# TQFP-100_to_breadboard-100.net
KiCad netlist of a schematic drawn in EAGLE
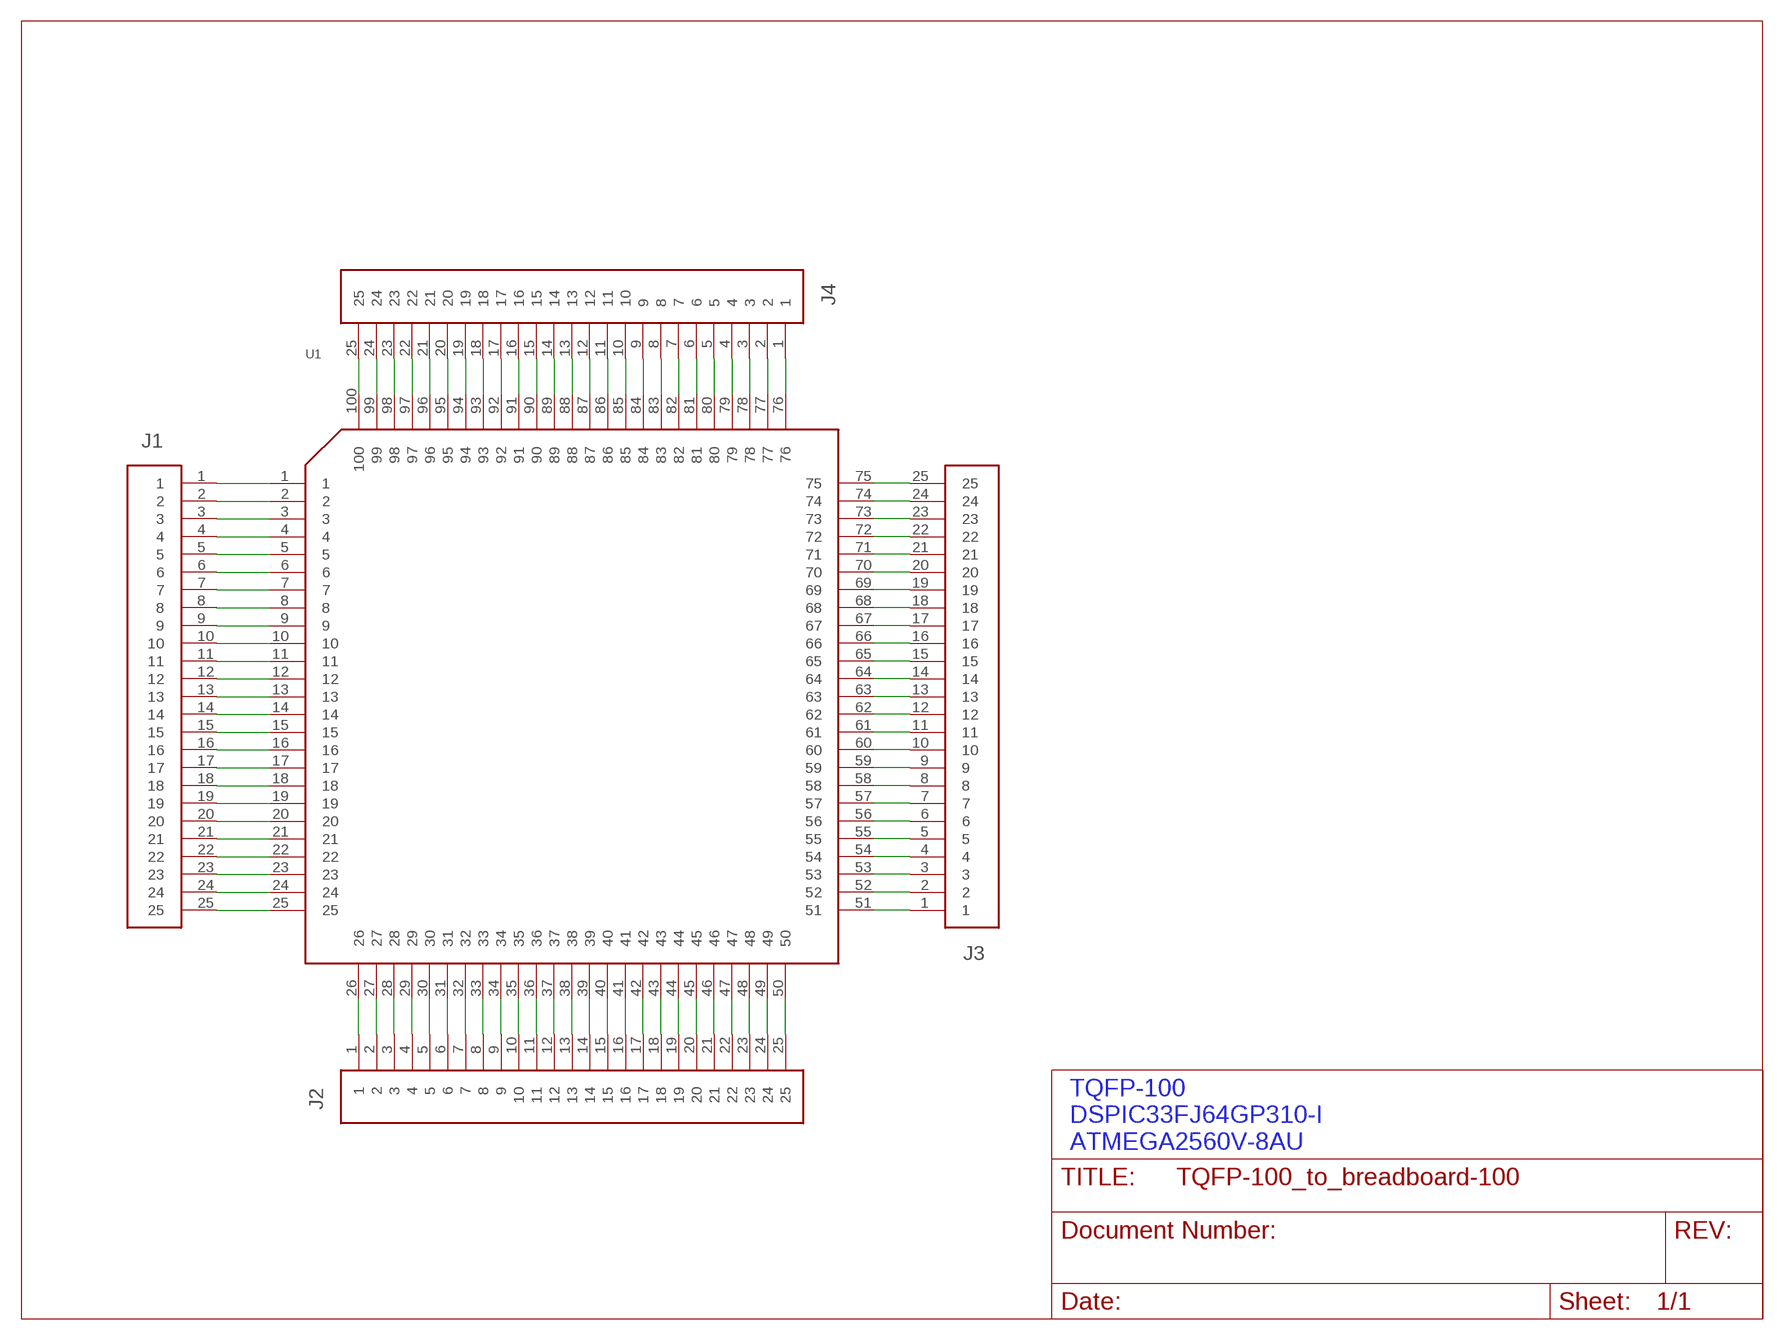
[diagram p0: schematic, sheet 1]

(export (version "E")
  (design (tool "Eeschema 10.0.6"))
  (components
    (comp (ref "J1")
      (value "CONNECTOR_25")
      (footprint "eagle-import:68000-125HLF")
      (libsource (lib "eagle-import") (part "CONNECTOR_25"))
    )
    (comp (ref "J2")
      (value "CONNECTOR_25_NO_SQUARE")
      (footprint "eagle-import:68000-125HLF_NO_SQUARE")
      (libsource (lib "eagle-import") (part "CONNECTOR_25_NO_SQUARE"))
    )
    (comp (ref "J3")
      (value "CONNECTOR_25_NO_SQUARE")
      (footprint "eagle-import:68000-125HLF_NO_SQUARE")
      (libsource (lib "eagle-import") (part "CONNECTOR_25_NO_SQUARE"))
    )
    (comp (ref "J4")
      (value "CONNECTOR_25_NO_SQUARE")
      (footprint "eagle-import:68000-125HLF_NO_SQUARE")
      (libsource (lib "eagle-import") (part "CONNECTOR_25_NO_SQUARE"))
    )
    (comp (ref "U1")
      (value "IC-GENERIC-100-TQFP")
      (footprint "eagle-import:QFP40P1400X1400X120-100N")
      (libsource (lib "eagle-import") (part "IC-GENERIC-100-TQFP"))
    )
  )
  (nets
    (net (code "1") (name "Net-(J1-Pad1)") (class "Default")
      (node (ref "J1") (pin "1") (pinfunction "1_1") (pintype "bidirectional"))
      (node (ref "U1") (pin "1") (pinfunction "1_1") (pintype "bidirectional"))
    )
    (net (code "2") (name "Net-(J1-Pad2)") (class "Default")
      (node (ref "J1") (pin "2") (pinfunction "2_2") (pintype "bidirectional"))
      (node (ref "U1") (pin "2") (pinfunction "2_2") (pintype "bidirectional"))
    )
    (net (code "3") (name "Net-(J1-Pad3)") (class "Default")
      (node (ref "J1") (pin "3") (pinfunction "3_3") (pintype "bidirectional"))
      (node (ref "U1") (pin "3") (pinfunction "3_3") (pintype "bidirectional"))
    )
    (net (code "4") (name "Net-(J1-Pad4)") (class "Default")
      (node (ref "J1") (pin "4") (pinfunction "4_4") (pintype "bidirectional"))
      (node (ref "U1") (pin "4") (pinfunction "4_4") (pintype "bidirectional"))
    )
    (net (code "5") (name "Net-(J1-Pad5)") (class "Default")
      (node (ref "J1") (pin "5") (pinfunction "5_5") (pintype "bidirectional"))
      (node (ref "U1") (pin "5") (pinfunction "5_5") (pintype "bidirectional"))
    )
    (net (code "6") (name "Net-(J1-Pad6)") (class "Default")
      (node (ref "J1") (pin "6") (pinfunction "6_6") (pintype "bidirectional"))
      (node (ref "U1") (pin "6") (pinfunction "6_6") (pintype "bidirectional"))
    )
    (net (code "7") (name "Net-(J1-Pad7)") (class "Default")
      (node (ref "J1") (pin "7") (pinfunction "7_7") (pintype "bidirectional"))
      (node (ref "U1") (pin "7") (pinfunction "7_7") (pintype "bidirectional"))
    )
    (net (code "8") (name "Net-(J1-Pad8)") (class "Default")
      (node (ref "J1") (pin "8") (pinfunction "8_8") (pintype "bidirectional"))
      (node (ref "U1") (pin "8") (pinfunction "8_8") (pintype "bidirectional"))
    )
    (net (code "9") (name "Net-(J1-Pad9)") (class "Default")
      (node (ref "J1") (pin "9") (pinfunction "9_9") (pintype "bidirectional"))
      (node (ref "U1") (pin "9") (pinfunction "9_9") (pintype "bidirectional"))
    )
    (net (code "10") (name "Net-(J1-Pad10)") (class "Default")
      (node (ref "J1") (pin "10") (pinfunction "10_10") (pintype "bidirectional"))
      (node (ref "U1") (pin "10") (pinfunction "10_10") (pintype "bidirectional"))
    )
    (net (code "11") (name "Net-(J1-Pad11)") (class "Default")
      (node (ref "J1") (pin "11") (pinfunction "11_11") (pintype "bidirectional"))
      (node (ref "U1") (pin "11") (pinfunction "11_11") (pintype "bidirectional"))
    )
    (net (code "12") (name "Net-(J1-Pad12)") (class "Default")
      (node (ref "J1") (pin "12") (pinfunction "12_12") (pintype "bidirectional"))
      (node (ref "U1") (pin "12") (pinfunction "12_12") (pintype "bidirectional"))
    )
    (net (code "13") (name "Net-(J1-Pad13)") (class "Default")
      (node (ref "J1") (pin "13") (pinfunction "13_13") (pintype "bidirectional"))
      (node (ref "U1") (pin "13") (pinfunction "13_13") (pintype "bidirectional"))
    )
    (net (code "14") (name "Net-(J1-Pad14)") (class "Default")
      (node (ref "J1") (pin "14") (pinfunction "14_14") (pintype "bidirectional"))
      (node (ref "U1") (pin "14") (pinfunction "14_14") (pintype "bidirectional"))
    )
    (net (code "15") (name "Net-(J1-Pad15)") (class "Default")
      (node (ref "J1") (pin "15") (pinfunction "15_15") (pintype "bidirectional"))
      (node (ref "U1") (pin "15") (pinfunction "15_15") (pintype "bidirectional"))
    )
    (net (code "16") (name "Net-(J1-Pad16)") (class "Default")
      (node (ref "J1") (pin "16") (pinfunction "16_16") (pintype "bidirectional"))
      (node (ref "U1") (pin "16") (pinfunction "16_16") (pintype "bidirectional"))
    )
    (net (code "17") (name "Net-(J1-Pad17)") (class "Default")
      (node (ref "J1") (pin "17") (pinfunction "17_17") (pintype "bidirectional"))
      (node (ref "U1") (pin "17") (pinfunction "17_17") (pintype "bidirectional"))
    )
    (net (code "18") (name "Net-(J1-Pad18)") (class "Default")
      (node (ref "J1") (pin "18") (pinfunction "18_18") (pintype "bidirectional"))
      (node (ref "U1") (pin "18") (pinfunction "18_18") (pintype "bidirectional"))
    )
    (net (code "19") (name "Net-(J1-Pad19)") (class "Default")
      (node (ref "J1") (pin "19") (pinfunction "19_19") (pintype "bidirectional"))
      (node (ref "U1") (pin "19") (pinfunction "19_19") (pintype "bidirectional"))
    )
    (net (code "20") (name "Net-(J1-Pad20)") (class "Default")
      (node (ref "J1") (pin "20") (pinfunction "20_20") (pintype "bidirectional"))
      (node (ref "U1") (pin "20") (pinfunction "20_20") (pintype "bidirectional"))
    )
    (net (code "21") (name "Net-(J1-Pad21)") (class "Default")
      (node (ref "J1") (pin "21") (pinfunction "21_21") (pintype "bidirectional"))
      (node (ref "U1") (pin "21") (pinfunction "21_21") (pintype "bidirectional"))
    )
    (net (code "22") (name "Net-(J1-Pad22)") (class "Default")
      (node (ref "J1") (pin "22") (pinfunction "22_22") (pintype "bidirectional"))
      (node (ref "U1") (pin "22") (pinfunction "22_22") (pintype "bidirectional"))
    )
    (net (code "23") (name "Net-(J1-Pad23)") (class "Default")
      (node (ref "J1") (pin "23") (pinfunction "23_23") (pintype "bidirectional"))
      (node (ref "U1") (pin "23") (pinfunction "23_23") (pintype "bidirectional"))
    )
    (net (code "24") (name "Net-(J1-Pad24)") (class "Default")
      (node (ref "J1") (pin "24") (pinfunction "24_24") (pintype "bidirectional"))
      (node (ref "U1") (pin "24") (pinfunction "24_24") (pintype "bidirectional"))
    )
    (net (code "25") (name "Net-(J1-Pad25)") (class "Default")
      (node (ref "J1") (pin "25") (pinfunction "25_25") (pintype "bidirectional"))
      (node (ref "U1") (pin "25") (pinfunction "25_25") (pintype "bidirectional"))
    )
    (net (code "26") (name "Net-(J2-Pad1)") (class "Default")
      (node (ref "J2") (pin "1") (pinfunction "1_1") (pintype "bidirectional"))
      (node (ref "U1") (pin "26") (pinfunction "26_26") (pintype "bidirectional"))
    )
    (net (code "27") (name "Net-(J2-Pad2)") (class "Default")
      (node (ref "J2") (pin "2") (pinfunction "2_2") (pintype "bidirectional"))
      (node (ref "U1") (pin "27") (pinfunction "27_27") (pintype "bidirectional"))
    )
    (net (code "28") (name "Net-(J2-Pad3)") (class "Default")
      (node (ref "J2") (pin "3") (pinfunction "3_3") (pintype "bidirectional"))
      (node (ref "U1") (pin "28") (pinfunction "28_28") (pintype "bidirectional"))
    )
    (net (code "29") (name "Net-(J2-Pad4)") (class "Default")
      (node (ref "J2") (pin "4") (pinfunction "4_4") (pintype "bidirectional"))
      (node (ref "U1") (pin "29") (pinfunction "29_29") (pintype "bidirectional"))
    )
    (net (code "30") (name "Net-(J2-Pad5)") (class "Default")
      (node (ref "J2") (pin "5") (pinfunction "5_5") (pintype "bidirectional"))
      (node (ref "U1") (pin "30") (pinfunction "30_30") (pintype "bidirectional"))
    )
    (net (code "31") (name "Net-(J2-Pad6)") (class "Default")
      (node (ref "J2") (pin "6") (pinfunction "6_6") (pintype "bidirectional"))
      (node (ref "U1") (pin "31") (pinfunction "31_31") (pintype "bidirectional"))
    )
    (net (code "32") (name "Net-(J2-Pad7)") (class "Default")
      (node (ref "J2") (pin "7") (pinfunction "7_7") (pintype "bidirectional"))
      (node (ref "U1") (pin "32") (pinfunction "32_32") (pintype "bidirectional"))
    )
    (net (code "33") (name "Net-(J2-Pad8)") (class "Default")
      (node (ref "J2") (pin "8") (pinfunction "8_8") (pintype "bidirectional"))
      (node (ref "U1") (pin "33") (pinfunction "33_33") (pintype "bidirectional"))
    )
    (net (code "34") (name "Net-(J2-Pad9)") (class "Default")
      (node (ref "J2") (pin "9") (pinfunction "9_9") (pintype "bidirectional"))
      (node (ref "U1") (pin "34") (pinfunction "34_34") (pintype "bidirectional"))
    )
    (net (code "35") (name "Net-(J2-Pad10)") (class "Default")
      (node (ref "J2") (pin "10") (pinfunction "10_10") (pintype "bidirectional"))
      (node (ref "U1") (pin "35") (pinfunction "35_35") (pintype "bidirectional"))
    )
    (net (code "36") (name "Net-(J2-Pad11)") (class "Default")
      (node (ref "J2") (pin "11") (pinfunction "11_11") (pintype "bidirectional"))
      (node (ref "U1") (pin "36") (pinfunction "36_36") (pintype "bidirectional"))
    )
    (net (code "37") (name "Net-(J2-Pad12)") (class "Default")
      (node (ref "J2") (pin "12") (pinfunction "12_12") (pintype "bidirectional"))
      (node (ref "U1") (pin "37") (pinfunction "37_37") (pintype "bidirectional"))
    )
    (net (code "38") (name "Net-(J2-Pad13)") (class "Default")
      (node (ref "J2") (pin "13") (pinfunction "13_13") (pintype "bidirectional"))
      (node (ref "U1") (pin "38") (pinfunction "38_38") (pintype "bidirectional"))
    )
    (net (code "39") (name "Net-(J2-Pad14)") (class "Default")
      (node (ref "J2") (pin "14") (pinfunction "14_14") (pintype "bidirectional"))
      (node (ref "U1") (pin "39") (pinfunction "39_39") (pintype "bidirectional"))
    )
    (net (code "40") (name "Net-(J2-Pad15)") (class "Default")
      (node (ref "J2") (pin "15") (pinfunction "15_15") (pintype "bidirectional"))
      (node (ref "U1") (pin "40") (pinfunction "40_40") (pintype "bidirectional"))
    )
    (net (code "41") (name "Net-(J2-Pad16)") (class "Default")
      (node (ref "J2") (pin "16") (pinfunction "16_16") (pintype "bidirectional"))
      (node (ref "U1") (pin "41") (pinfunction "41_41") (pintype "bidirectional"))
    )
    (net (code "42") (name "Net-(J2-Pad17)") (class "Default")
      (node (ref "J2") (pin "17") (pinfunction "17_17") (pintype "bidirectional"))
      (node (ref "U1") (pin "42") (pinfunction "42_42") (pintype "bidirectional"))
    )
    (net (code "43") (name "Net-(J2-Pad18)") (class "Default")
      (node (ref "J2") (pin "18") (pinfunction "18_18") (pintype "bidirectional"))
      (node (ref "U1") (pin "43") (pinfunction "43_43") (pintype "bidirectional"))
    )
    (net (code "44") (name "Net-(J2-Pad19)") (class "Default")
      (node (ref "J2") (pin "19") (pinfunction "19_19") (pintype "bidirectional"))
      (node (ref "U1") (pin "44") (pinfunction "44_44") (pintype "bidirectional"))
    )
    (net (code "45") (name "Net-(J2-Pad20)") (class "Default")
      (node (ref "J2") (pin "20") (pinfunction "20_20") (pintype "bidirectional"))
      (node (ref "U1") (pin "45") (pinfunction "45_45") (pintype "bidirectional"))
    )
    (net (code "46") (name "Net-(J2-Pad21)") (class "Default")
      (node (ref "J2") (pin "21") (pinfunction "21_21") (pintype "bidirectional"))
      (node (ref "U1") (pin "46") (pinfunction "46_46") (pintype "bidirectional"))
    )
    (net (code "47") (name "Net-(J2-Pad22)") (class "Default")
      (node (ref "J2") (pin "22") (pinfunction "22_22") (pintype "bidirectional"))
      (node (ref "U1") (pin "47") (pinfunction "47_47") (pintype "bidirectional"))
    )
    (net (code "48") (name "Net-(J2-Pad23)") (class "Default")
      (node (ref "J2") (pin "23") (pinfunction "23_23") (pintype "bidirectional"))
      (node (ref "U1") (pin "48") (pinfunction "48_48") (pintype "bidirectional"))
    )
    (net (code "49") (name "Net-(J2-Pad24)") (class "Default")
      (node (ref "J2") (pin "24") (pinfunction "24_24") (pintype "bidirectional"))
      (node (ref "U1") (pin "49") (pinfunction "49_49") (pintype "bidirectional"))
    )
    (net (code "50") (name "Net-(J2-Pad25)") (class "Default")
      (node (ref "J2") (pin "25") (pinfunction "25_25") (pintype "bidirectional"))
      (node (ref "U1") (pin "50") (pinfunction "50_50") (pintype "bidirectional"))
    )
    (net (code "51") (name "Net-(J3-Pad1)") (class "Default")
      (node (ref "J3") (pin "1") (pinfunction "1_1") (pintype "bidirectional"))
      (node (ref "U1") (pin "51") (pinfunction "51_51") (pintype "bidirectional"))
    )
    (net (code "52") (name "Net-(J3-Pad2)") (class "Default")
      (node (ref "J3") (pin "2") (pinfunction "2_2") (pintype "bidirectional"))
      (node (ref "U1") (pin "52") (pinfunction "52_52") (pintype "bidirectional"))
    )
    (net (code "53") (name "Net-(J3-Pad3)") (class "Default")
      (node (ref "J3") (pin "3") (pinfunction "3_3") (pintype "bidirectional"))
      (node (ref "U1") (pin "53") (pinfunction "53_53") (pintype "bidirectional"))
    )
    (net (code "54") (name "Net-(J3-Pad4)") (class "Default")
      (node (ref "J3") (pin "4") (pinfunction "4_4") (pintype "bidirectional"))
      (node (ref "U1") (pin "54") (pinfunction "54_54") (pintype "bidirectional"))
    )
    (net (code "55") (name "Net-(J3-Pad5)") (class "Default")
      (node (ref "J3") (pin "5") (pinfunction "5_5") (pintype "bidirectional"))
      (node (ref "U1") (pin "55") (pinfunction "55_55") (pintype "bidirectional"))
    )
    (net (code "56") (name "Net-(J3-Pad6)") (class "Default")
      (node (ref "J3") (pin "6") (pinfunction "6_6") (pintype "bidirectional"))
      (node (ref "U1") (pin "56") (pinfunction "56_56") (pintype "bidirectional"))
    )
    (net (code "57") (name "Net-(J3-Pad7)") (class "Default")
      (node (ref "J3") (pin "7") (pinfunction "7_7") (pintype "bidirectional"))
      (node (ref "U1") (pin "57") (pinfunction "57_57") (pintype "bidirectional"))
    )
    (net (code "58") (name "Net-(J3-Pad8)") (class "Default")
      (node (ref "J3") (pin "8") (pinfunction "8_8") (pintype "bidirectional"))
      (node (ref "U1") (pin "58") (pinfunction "58_58") (pintype "bidirectional"))
    )
    (net (code "59") (name "Net-(J3-Pad9)") (class "Default")
      (node (ref "J3") (pin "9") (pinfunction "9_9") (pintype "bidirectional"))
      (node (ref "U1") (pin "59") (pinfunction "59_59") (pintype "bidirectional"))
    )
    (net (code "60") (name "Net-(J3-Pad10)") (class "Default")
      (node (ref "J3") (pin "10") (pinfunction "10_10") (pintype "bidirectional"))
      (node (ref "U1") (pin "60") (pinfunction "60_60") (pintype "bidirectional"))
    )
    (net (code "61") (name "Net-(J3-Pad11)") (class "Default")
      (node (ref "J3") (pin "11") (pinfunction "11_11") (pintype "bidirectional"))
      (node (ref "U1") (pin "61") (pinfunction "61_61") (pintype "bidirectional"))
    )
    (net (code "62") (name "Net-(J3-Pad12)") (class "Default")
      (node (ref "J3") (pin "12") (pinfunction "12_12") (pintype "bidirectional"))
      (node (ref "U1") (pin "62") (pinfunction "62_62") (pintype "bidirectional"))
    )
    (net (code "63") (name "Net-(J3-Pad13)") (class "Default")
      (node (ref "J3") (pin "13") (pinfunction "13_13") (pintype "bidirectional"))
      (node (ref "U1") (pin "63") (pinfunction "63_63") (pintype "bidirectional"))
    )
    (net (code "64") (name "Net-(J3-Pad14)") (class "Default")
      (node (ref "J3") (pin "14") (pinfunction "14_14") (pintype "bidirectional"))
      (node (ref "U1") (pin "64") (pinfunction "64_64") (pintype "bidirectional"))
    )
    (net (code "65") (name "Net-(J3-Pad15)") (class "Default")
      (node (ref "J3") (pin "15") (pinfunction "15_15") (pintype "bidirectional"))
      (node (ref "U1") (pin "65") (pinfunction "65_65") (pintype "bidirectional"))
    )
    (net (code "66") (name "Net-(J3-Pad16)") (class "Default")
      (node (ref "J3") (pin "16") (pinfunction "16_16") (pintype "bidirectional"))
      (node (ref "U1") (pin "66") (pinfunction "66_66") (pintype "bidirectional"))
    )
    (net (code "67") (name "Net-(J3-Pad17)") (class "Default")
      (node (ref "J3") (pin "17") (pinfunction "17_17") (pintype "bidirectional"))
      (node (ref "U1") (pin "67") (pinfunction "67_67") (pintype "bidirectional"))
    )
    (net (code "68") (name "Net-(J3-Pad18)") (class "Default")
      (node (ref "J3") (pin "18") (pinfunction "18_18") (pintype "bidirectional"))
      (node (ref "U1") (pin "68") (pinfunction "68_68") (pintype "bidirectional"))
    )
    (net (code "69") (name "Net-(J3-Pad19)") (class "Default")
      (node (ref "J3") (pin "19") (pinfunction "19_19") (pintype "bidirectional"))
      (node (ref "U1") (pin "69") (pinfunction "69_69") (pintype "bidirectional"))
    )
    (net (code "70") (name "Net-(J3-Pad20)") (class "Default")
      (node (ref "J3") (pin "20") (pinfunction "20_20") (pintype "bidirectional"))
      (node (ref "U1") (pin "70") (pinfunction "70_70") (pintype "bidirectional"))
    )
    (net (code "71") (name "Net-(J3-Pad21)") (class "Default")
      (node (ref "J3") (pin "21") (pinfunction "21_21") (pintype "bidirectional"))
      (node (ref "U1") (pin "71") (pinfunction "71_71") (pintype "bidirectional"))
    )
    (net (code "72") (name "Net-(J3-Pad22)") (class "Default")
      (node (ref "J3") (pin "22") (pinfunction "22_22") (pintype "bidirectional"))
      (node (ref "U1") (pin "72") (pinfunction "72_72") (pintype "bidirectional"))
    )
    (net (code "73") (name "Net-(J3-Pad23)") (class "Default")
      (node (ref "J3") (pin "23") (pinfunction "23_23") (pintype "bidirectional"))
      (node (ref "U1") (pin "73") (pinfunction "73_73") (pintype "bidirectional"))
    )
    (net (code "74") (name "Net-(J3-Pad24)") (class "Default")
      (node (ref "J3") (pin "24") (pinfunction "24_24") (pintype "bidirectional"))
      (node (ref "U1") (pin "74") (pinfunction "74_74") (pintype "bidirectional"))
    )
    (net (code "75") (name "Net-(J3-Pad25)") (class "Default")
      (node (ref "J3") (pin "25") (pinfunction "25_25") (pintype "bidirectional"))
      (node (ref "U1") (pin "75") (pinfunction "75_75") (pintype "bidirectional"))
    )
    (net (code "76") (name "Net-(J4-Pad1)") (class "Default")
      (node (ref "J4") (pin "1") (pinfunction "1_1") (pintype "bidirectional"))
      (node (ref "U1") (pin "76") (pinfunction "76_76") (pintype "bidirectional"))
    )
    (net (code "77") (name "Net-(J4-Pad2)") (class "Default")
      (node (ref "J4") (pin "2") (pinfunction "2_2") (pintype "bidirectional"))
      (node (ref "U1") (pin "77") (pinfunction "77_77") (pintype "bidirectional"))
    )
    (net (code "78") (name "Net-(J4-Pad3)") (class "Default")
      (node (ref "J4") (pin "3") (pinfunction "3_3") (pintype "bidirectional"))
      (node (ref "U1") (pin "78") (pinfunction "78_78") (pintype "bidirectional"))
    )
    (net (code "79") (name "Net-(J4-Pad4)") (class "Default")
      (node (ref "J4") (pin "4") (pinfunction "4_4") (pintype "bidirectional"))
      (node (ref "U1") (pin "79") (pinfunction "79_79") (pintype "bidirectional"))
    )
    (net (code "80") (name "Net-(J4-Pad5)") (class "Default")
      (node (ref "J4") (pin "5") (pinfunction "5_5") (pintype "bidirectional"))
      (node (ref "U1") (pin "80") (pinfunction "80_80") (pintype "bidirectional"))
    )
    (net (code "81") (name "Net-(J4-Pad6)") (class "Default")
      (node (ref "J4") (pin "6") (pinfunction "6_6") (pintype "bidirectional"))
      (node (ref "U1") (pin "81") (pinfunction "81_81") (pintype "bidirectional"))
    )
    (net (code "82") (name "Net-(J4-Pad7)") (class "Default")
      (node (ref "J4") (pin "7") (pinfunction "7_7") (pintype "bidirectional"))
      (node (ref "U1") (pin "82") (pinfunction "82_82") (pintype "bidirectional"))
    )
    (net (code "83") (name "Net-(J4-Pad8)") (class "Default")
      (node (ref "J4") (pin "8") (pinfunction "8_8") (pintype "bidirectional"))
      (node (ref "U1") (pin "83") (pinfunction "83_83") (pintype "bidirectional"))
    )
    (net (code "84") (name "Net-(J4-Pad9)") (class "Default")
      (node (ref "J4") (pin "9") (pinfunction "9_9") (pintype "bidirectional"))
      (node (ref "U1") (pin "84") (pinfunction "84_84") (pintype "bidirectional"))
    )
    (net (code "85") (name "Net-(J4-Pad10)") (class "Default")
      (node (ref "J4") (pin "10") (pinfunction "10_10") (pintype "bidirectional"))
      (node (ref "U1") (pin "85") (pinfunction "85_85") (pintype "bidirectional"))
    )
    (net (code "86") (name "Net-(J4-Pad11)") (class "Default")
      (node (ref "J4") (pin "11") (pinfunction "11_11") (pintype "bidirectional"))
      (node (ref "U1") (pin "86") (pinfunction "86_86") (pintype "bidirectional"))
    )
    (net (code "87") (name "Net-(J4-Pad12)") (class "Default")
      (node (ref "J4") (pin "12") (pinfunction "12_12") (pintype "bidirectional"))
      (node (ref "U1") (pin "87") (pinfunction "87_87") (pintype "bidirectional"))
    )
    (net (code "88") (name "Net-(J4-Pad13)") (class "Default")
      (node (ref "J4") (pin "13") (pinfunction "13_13") (pintype "bidirectional"))
      (node (ref "U1") (pin "88") (pinfunction "88_88") (pintype "bidirectional"))
    )
    (net (code "89") (name "Net-(J4-Pad14)") (class "Default")
      (node (ref "J4") (pin "14") (pinfunction "14_14") (pintype "bidirectional"))
      (node (ref "U1") (pin "89") (pinfunction "89_89") (pintype "bidirectional"))
    )
    (net (code "90") (name "Net-(J4-Pad15)") (class "Default")
      (node (ref "J4") (pin "15") (pinfunction "15_15") (pintype "bidirectional"))
      (node (ref "U1") (pin "90") (pinfunction "90_90") (pintype "bidirectional"))
    )
    (net (code "91") (name "Net-(J4-Pad16)") (class "Default")
      (node (ref "J4") (pin "16") (pinfunction "16_16") (pintype "bidirectional"))
      (node (ref "U1") (pin "91") (pinfunction "91_91") (pintype "bidirectional"))
    )
    (net (code "92") (name "Net-(J4-Pad17)") (class "Default")
      (node (ref "J4") (pin "17") (pinfunction "17_17") (pintype "bidirectional"))
      (node (ref "U1") (pin "92") (pinfunction "92_92") (pintype "bidirectional"))
    )
    (net (code "93") (name "Net-(J4-Pad18)") (class "Default")
      (node (ref "J4") (pin "18") (pinfunction "18_18") (pintype "bidirectional"))
      (node (ref "U1") (pin "93") (pinfunction "93_93") (pintype "bidirectional"))
    )
    (net (code "94") (name "Net-(J4-Pad19)") (class "Default")
      (node (ref "J4") (pin "19") (pinfunction "19_19") (pintype "bidirectional"))
      (node (ref "U1") (pin "94") (pinfunction "94_94") (pintype "bidirectional"))
    )
    (net (code "95") (name "Net-(J4-Pad20)") (class "Default")
      (node (ref "J4") (pin "20") (pinfunction "20_20") (pintype "bidirectional"))
      (node (ref "U1") (pin "95") (pinfunction "95_95") (pintype "bidirectional"))
    )
    (net (code "96") (name "Net-(J4-Pad21)") (class "Default")
      (node (ref "J4") (pin "21") (pinfunction "21_21") (pintype "bidirectional"))
      (node (ref "U1") (pin "96") (pinfunction "96_96") (pintype "bidirectional"))
    )
    (net (code "97") (name "Net-(J4-Pad22)") (class "Default")
      (node (ref "J4") (pin "22") (pinfunction "22_22") (pintype "bidirectional"))
      (node (ref "U1") (pin "97") (pinfunction "97_97") (pintype "bidirectional"))
    )
    (net (code "98") (name "Net-(J4-Pad23)") (class "Default")
      (node (ref "J4") (pin "23") (pinfunction "23_23") (pintype "bidirectional"))
      (node (ref "U1") (pin "98") (pinfunction "98_98") (pintype "bidirectional"))
    )
    (net (code "99") (name "Net-(J4-Pad24)") (class "Default")
      (node (ref "J4") (pin "24") (pinfunction "24_24") (pintype "bidirectional"))
      (node (ref "U1") (pin "99") (pinfunction "99_99") (pintype "bidirectional"))
    )
    (net (code "100") (name "Net-(J4-Pad25)") (class "Default")
      (node (ref "J4") (pin "25") (pinfunction "25_25") (pintype "bidirectional"))
      (node (ref "U1") (pin "100") (pinfunction "100_100") (pintype "bidirectional"))
    )
  )
)
